# originbot_controller.net
KiCad netlist of a schematic drawn in Altium Designer
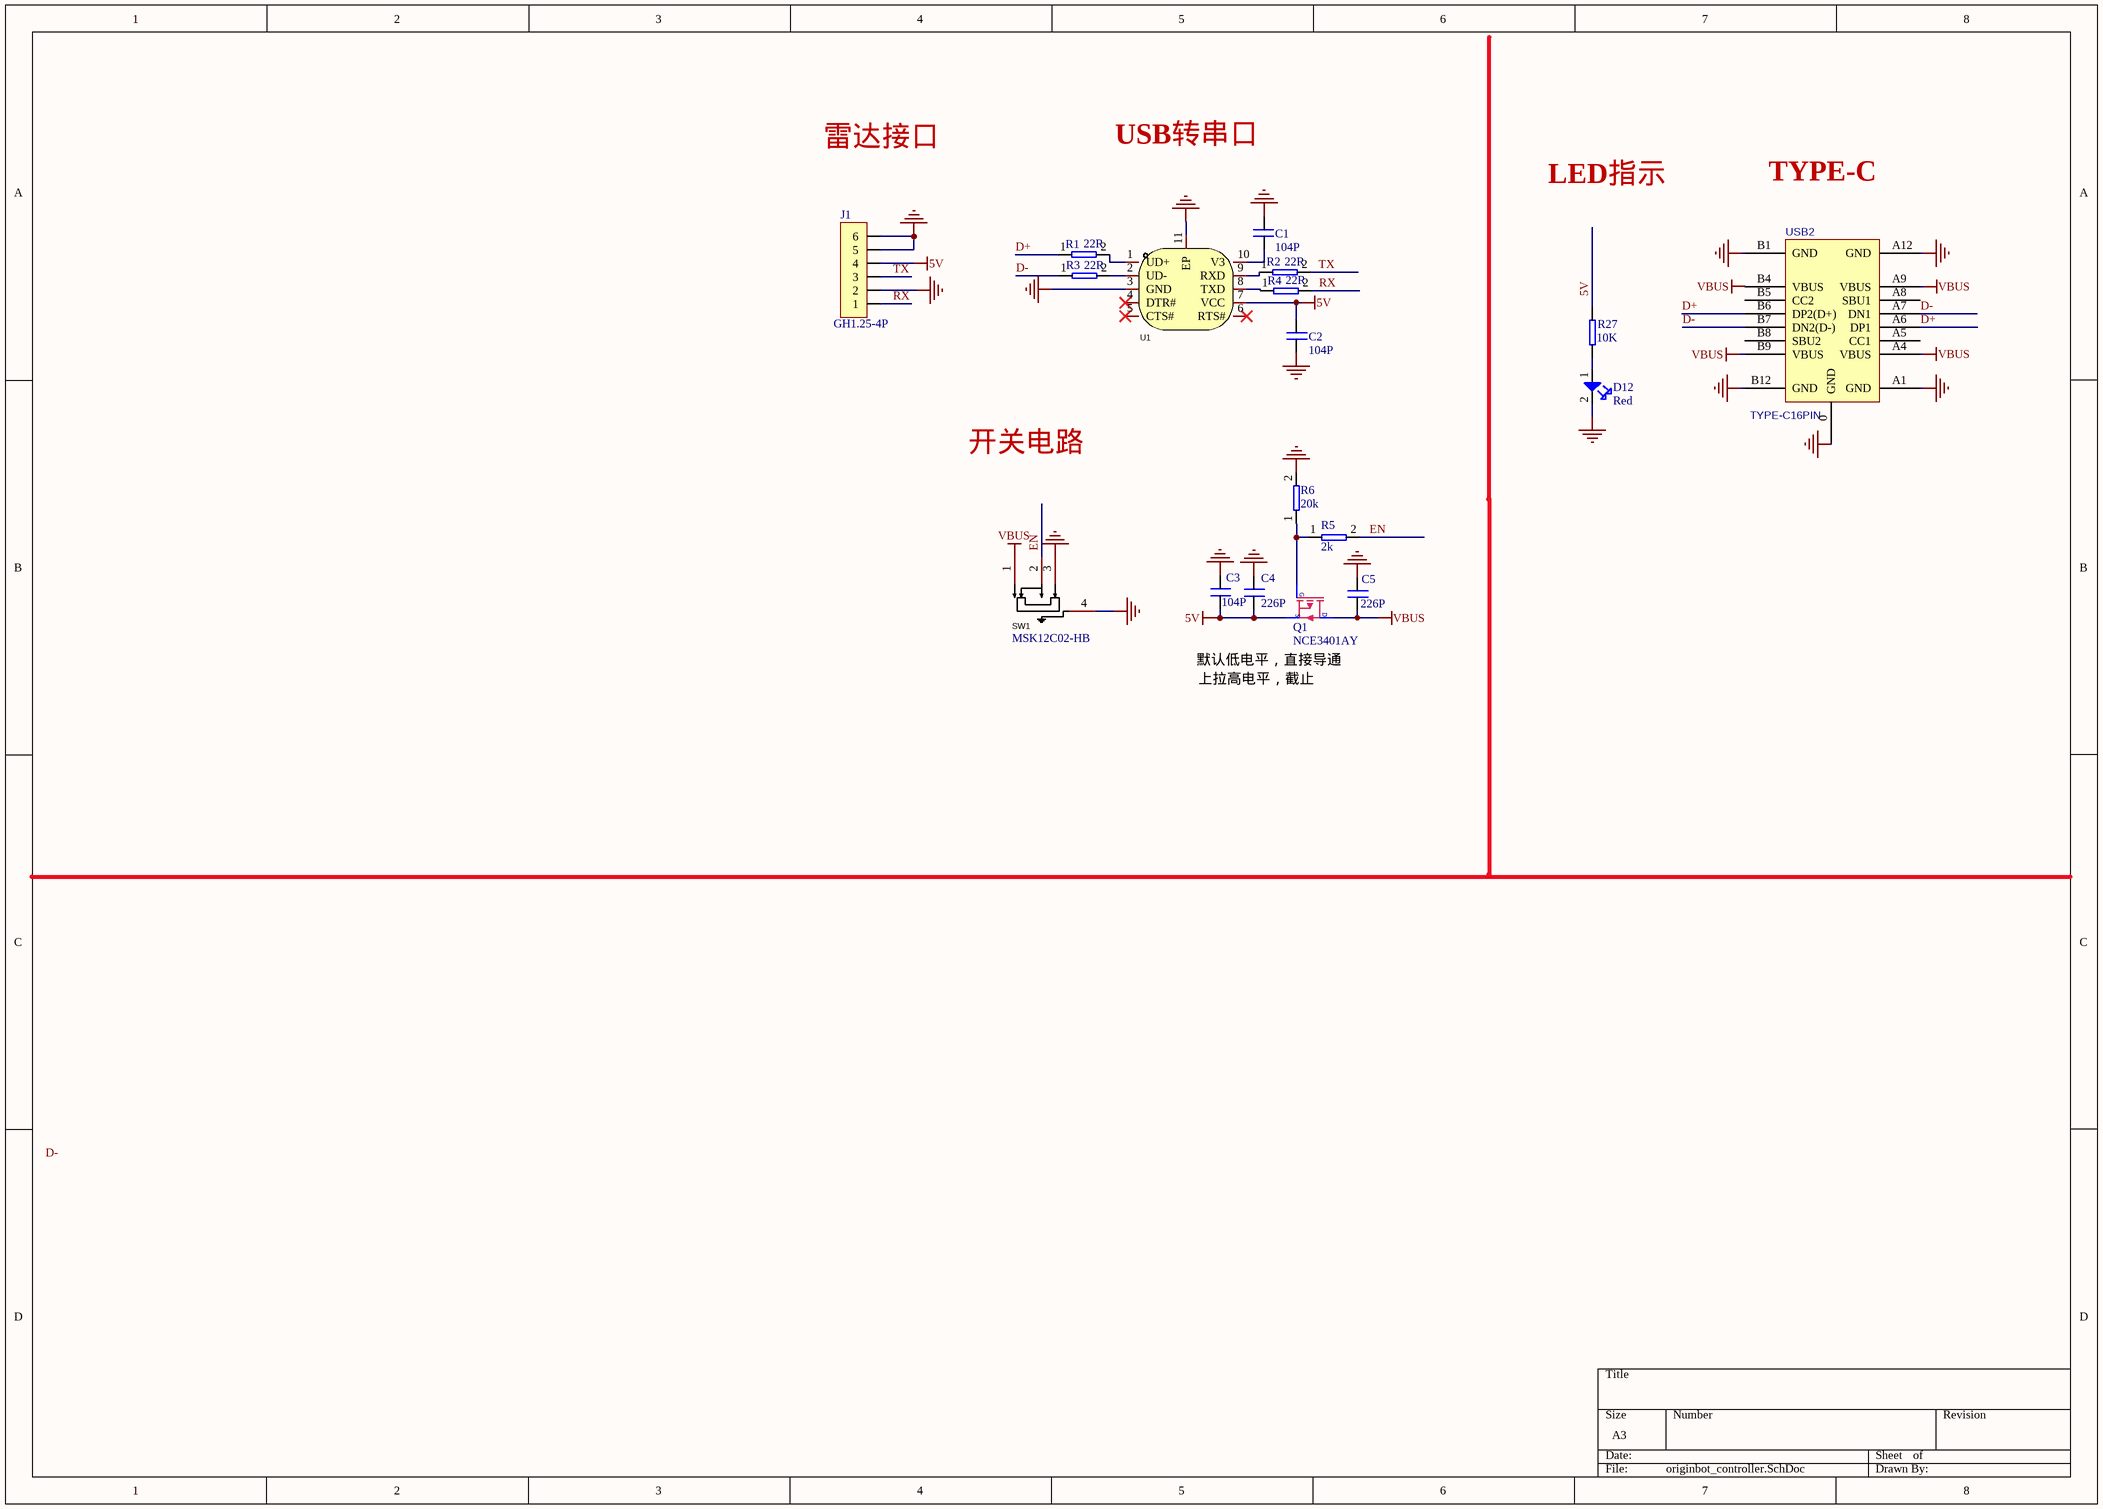
[diagram p0: originbot_controller.SchDoc]

(export (version "E")
  (design (tool "Eeschema 10.0.6"))
  (components
    (comp (ref "C1") (value "104P") (footprint "C0603") (libsource (lib "CZ 3D") (part "Cap")))
    (comp (ref "C2") (value "104P") (footprint "C0603") (libsource (lib "CZ 3D") (part "Cap")))
    (comp (ref "C3") (value "104P") (footprint "C0603") (libsource (lib "CZ 3D") (part "Cap")))
    (comp (ref "C4") (value "226P") (footprint "C0603") (libsource (lib "CZ 3D") (part "Cap")))
    (comp (ref "C5") (value "226P") (footprint "C0603") (libsource (lib "CZ 3D") (part "Cap")))
    (comp (ref "D12") (value "Red") (footprint "D0603-R") (libsource (lib "CZ 3D") (part "LED-贴片")))
    (comp (ref "J1") (value "GH1.25-4P") (footprint "GH1.25MM") (libsource (lib "CZ 3D") (part "Header6")))
    (comp (ref "Q1") (value "NCE3401AY") (footprint "SOT-23-3") (libsource (lib "CZ 3D") (part "PMOS")))
    (comp (ref "R1") (value "22R") (footprint "R0603") (libsource (lib "51+arm") (part "RN")))
    (comp (ref "R2") (value "22R") (footprint "R0603") (libsource (lib "51+arm") (part "RN")))
    (comp (ref "R3") (value "22R") (footprint "R0603") (libsource (lib "51+arm") (part "RN")))
    (comp (ref "R4") (value "22R") (footprint "R0603") (libsource (lib "51+arm") (part "RN")))
    (comp (ref "R5") (value "2k") (footprint "R0603") (libsource (lib "51+arm") (part "RN")))
    (comp (ref "R6") (value "20k") (footprint "R0603") (libsource (lib "51+arm") (part "RN")))
    (comp (ref "R27") (value "10K") (footprint "R0603") (libsource (lib "CZ 3D") (part "Res")))
    (comp (ref "SW1")
      (value "MSK12C02-HB")
      (footprint "MSK12C02-HB")
      (fields (field (name "MANUFACTURER") "SHOU HAN(�׺�)"))
      (libsource (lib "CZ 3D") (part "MSK12C02-HB"))
    )
    (comp (ref "U1")
      (value "CH340K")
      (footprint "ESOP10")
      (fields (field (name "MANUFACTURER") "WCH(南京沁恒)"))
      (libsource (lib "CZ 3D") (part "CH340K"))
    )
    (comp (ref "USB2")
      (value "TYPE-C16PIN")
      (footprint "USB-C-SMD_TYPE-C16PIN")
      (fields (field (name "BOM_SUPPLIER PART") "C393939") (field (name "CONTRIBUTOR") "LCSC"))
      (libsource (lib "CZ 3D") (part "TYPE-C16PIN"))
    )
  )
  (nets
    (net (code "1") (name "/D+") (class "Default")
      (node (ref "R1") (pin "1") (pinfunction "1_1") (pintype "passive"))
      (node (ref "USB2") (pin "A6") (pinfunction "DP1_A6") (pintype "passive"))
      (node (ref "USB2") (pin "B6") (pinfunction "DP2(D+)_B6") (pintype "passive"))
    )
    (net (code "2") (name "/D-") (class "Default")
      (node (ref "R3") (pin "1") (pinfunction "1_1") (pintype "passive"))
      (node (ref "USB2") (pin "A7") (pinfunction "DN1_A7") (pintype "passive"))
      (node (ref "USB2") (pin "B7") (pinfunction "DN2(D-)_B7") (pintype "passive"))
    )
    (net (code "3") (name "/EN") (class "Default")
      (node (ref "R5") (pin "2") (pinfunction "2_2") (pintype "passive"))
      (node (ref "SW1") (pin "2") (pinfunction "2_2") (pintype "passive"))
    )
    (net (code "4") (name "/RX") (class "Default")
      (node (ref "J1") (pin "1") (pinfunction "1_1") (pintype "passive"))
      (node (ref "R4") (pin "2") (pinfunction "2_2") (pintype "passive"))
    )
    (net (code "5") (name "/TX") (class "Default")
      (node (ref "J1") (pin "3") (pinfunction "3_3") (pintype "passive"))
      (node (ref "R2") (pin "2") (pinfunction "2_2") (pintype "passive"))
    )
    (net (code "6") (name "5V") (class "Default")
      (node (ref "C2") (pin "2") (pinfunction "2_2") (pintype "passive"))
      (node (ref "C3") (pin "1") (pinfunction "1_1") (pintype "passive"))
      (node (ref "C4") (pin "1") (pinfunction "1_1") (pintype "passive"))
      (node (ref "J1") (pin "4") (pinfunction "4_4") (pintype "passive"))
      (node (ref "Q1") (pin "2") (pinfunction "2_2") (pintype "passive"))
      (node (ref "R27") (pin "2") (pinfunction "2_2") (pintype "passive"))
      (node (ref "U1") (pin "7") (pinfunction "VCC_7") (pintype "passive"))
    )
    (net (code "7") (name "GND") (class "Default")
      (node (ref "C1") (pin "1") (pinfunction "1_1") (pintype "passive"))
      (node (ref "C2") (pin "1") (pinfunction "1_1") (pintype "passive"))
      (node (ref "C3") (pin "2") (pinfunction "2_2") (pintype "passive"))
      (node (ref "C4") (pin "2") (pinfunction "2_2") (pintype "passive"))
      (node (ref "C5") (pin "2") (pinfunction "2_2") (pintype "passive"))
      (node (ref "D12") (pin "2") (pinfunction "2_2") (pintype "passive"))
      (node (ref "J1") (pin "2") (pinfunction "2_2") (pintype "passive"))
      (node (ref "J1") (pin "5") (pinfunction "5_5") (pintype "passive"))
      (node (ref "J1") (pin "6") (pinfunction "6_6") (pintype "passive"))
      (node (ref "R6") (pin "2") (pinfunction "2_2") (pintype "passive"))
      (node (ref "SW1") (pin "3") (pinfunction "3_3") (pintype "passive"))
      (node (ref "SW1") (pin "4") (pinfunction "4_4") (pintype "passive"))
      (node (ref "U1") (pin "11") (pinfunction "EP_11") (pintype "passive"))
      (node (ref "U1") (pin "3") (pinfunction "GND_3") (pintype "passive"))
      (node (ref "USB2") (pin "0") (pinfunction "GND_0") (pintype "passive"))
      (node (ref "USB2") (pin "A1") (pinfunction "GND_A1") (pintype "passive"))
      (node (ref "USB2") (pin "A12") (pinfunction "GND_A12") (pintype "passive"))
      (node (ref "USB2") (pin "B1") (pinfunction "GND_B1") (pintype "passive"))
      (node (ref "USB2") (pin "B12") (pinfunction "GND_B12") (pintype "passive"))
    )
    (net (code "8") (name "Net-(D12-Pad1)") (class "Default")
      (node (ref "D12") (pin "1") (pinfunction "1_1") (pintype "passive"))
      (node (ref "R27") (pin "1") (pinfunction "1_1") (pintype "passive"))
    )
    (net (code "9") (name "Net-(Q1-Pad1)") (class "Default")
      (node (ref "Q1") (pin "1") (pinfunction "1_1") (pintype "passive"))
      (node (ref "R5") (pin "1") (pinfunction "1_1") (pintype "passive"))
      (node (ref "R6") (pin "1") (pinfunction "1_1") (pintype "passive"))
    )
    (net (code "10") (name "Net-(U1-RXD)") (class "Default")
      (node (ref "R2") (pin "1") (pinfunction "1_1") (pintype "passive"))
      (node (ref "U1") (pin "9") (pinfunction "RXD_9") (pintype "passive"))
    )
    (net (code "11") (name "Net-(U1-TXD)") (class "Default")
      (node (ref "R4") (pin "1") (pinfunction "1_1") (pintype "passive"))
      (node (ref "U1") (pin "8") (pinfunction "TXD_8") (pintype "passive"))
    )
    (net (code "12") (name "Net-(U1-UD+)") (class "Default")
      (node (ref "R1") (pin "2") (pinfunction "2_2") (pintype "passive"))
      (node (ref "U1") (pin "1") (pinfunction "UD+_1") (pintype "passive"))
    )
    (net (code "13") (name "Net-(U1-UD-)") (class "Default")
      (node (ref "R3") (pin "2") (pinfunction "2_2") (pintype "passive"))
      (node (ref "U1") (pin "2") (pinfunction "UD-_2") (pintype "passive"))
    )
    (net (code "14") (name "Net-(U1-V3)") (class "Default")
      (node (ref "C1") (pin "2") (pinfunction "2_2") (pintype "passive"))
      (node (ref "U1") (pin "10") (pinfunction "V3_10") (pintype "passive"))
    )
    (net (code "15") (name "VBUS") (class "Default")
      (node (ref "C5") (pin "1") (pinfunction "1_1") (pintype "passive"))
      (node (ref "Q1") (pin "3") (pinfunction "3_3") (pintype "passive"))
      (node (ref "SW1") (pin "1") (pinfunction "1_1") (pintype "passive"))
      (node (ref "USB2") (pin "A4") (pinfunction "VBUS_A4") (pintype "passive"))
      (node (ref "USB2") (pin "A9") (pinfunction "VBUS_A9") (pintype "passive"))
      (node (ref "USB2") (pin "B4") (pinfunction "VBUS_B4") (pintype "passive"))
      (node (ref "USB2") (pin "B9") (pinfunction "VBUS_B9") (pintype "passive"))
    )
    (net (code "16") (name "unconnected-(U1-CTS#-Pad5)") (class "Default")
      (node (ref "U1") (pin "5") (pinfunction "CTS#_5") (pintype "passive+no_connect"))
    )
    (net (code "17") (name "unconnected-(U1-DTR#-Pad4)") (class "Default")
      (node (ref "U1") (pin "4") (pinfunction "DTR#_4") (pintype "passive+no_connect"))
    )
    (net (code "18") (name "unconnected-(U1-RTS#-Pad6)") (class "Default")
      (node (ref "U1") (pin "6") (pinfunction "RTS#_6") (pintype "passive+no_connect"))
    )
    (net (code "19") (name "unconnected-(USB2-CC1-PadA5)") (class "Default")
      (node (ref "USB2") (pin "A5") (pinfunction "CC1_A5") (pintype "passive"))
    )
    (net (code "20") (name "unconnected-(USB2-CC2-PadB5)") (class "Default")
      (node (ref "USB2") (pin "B5") (pinfunction "CC2_B5") (pintype "passive"))
    )
    (net (code "21") (name "unconnected-(USB2-SBU1-PadA8)") (class "Default")
      (node (ref "USB2") (pin "A8") (pinfunction "SBU1_A8") (pintype "passive"))
    )
    (net (code "22") (name "unconnected-(USB2-SBU2-PadB8)") (class "Default")
      (node (ref "USB2") (pin "B8") (pinfunction "SBU2_B8") (pintype "passive"))
    )
  )
)
